# D1MPIXEL.net
KiCad netlist of a schematic drawn in EAGLE
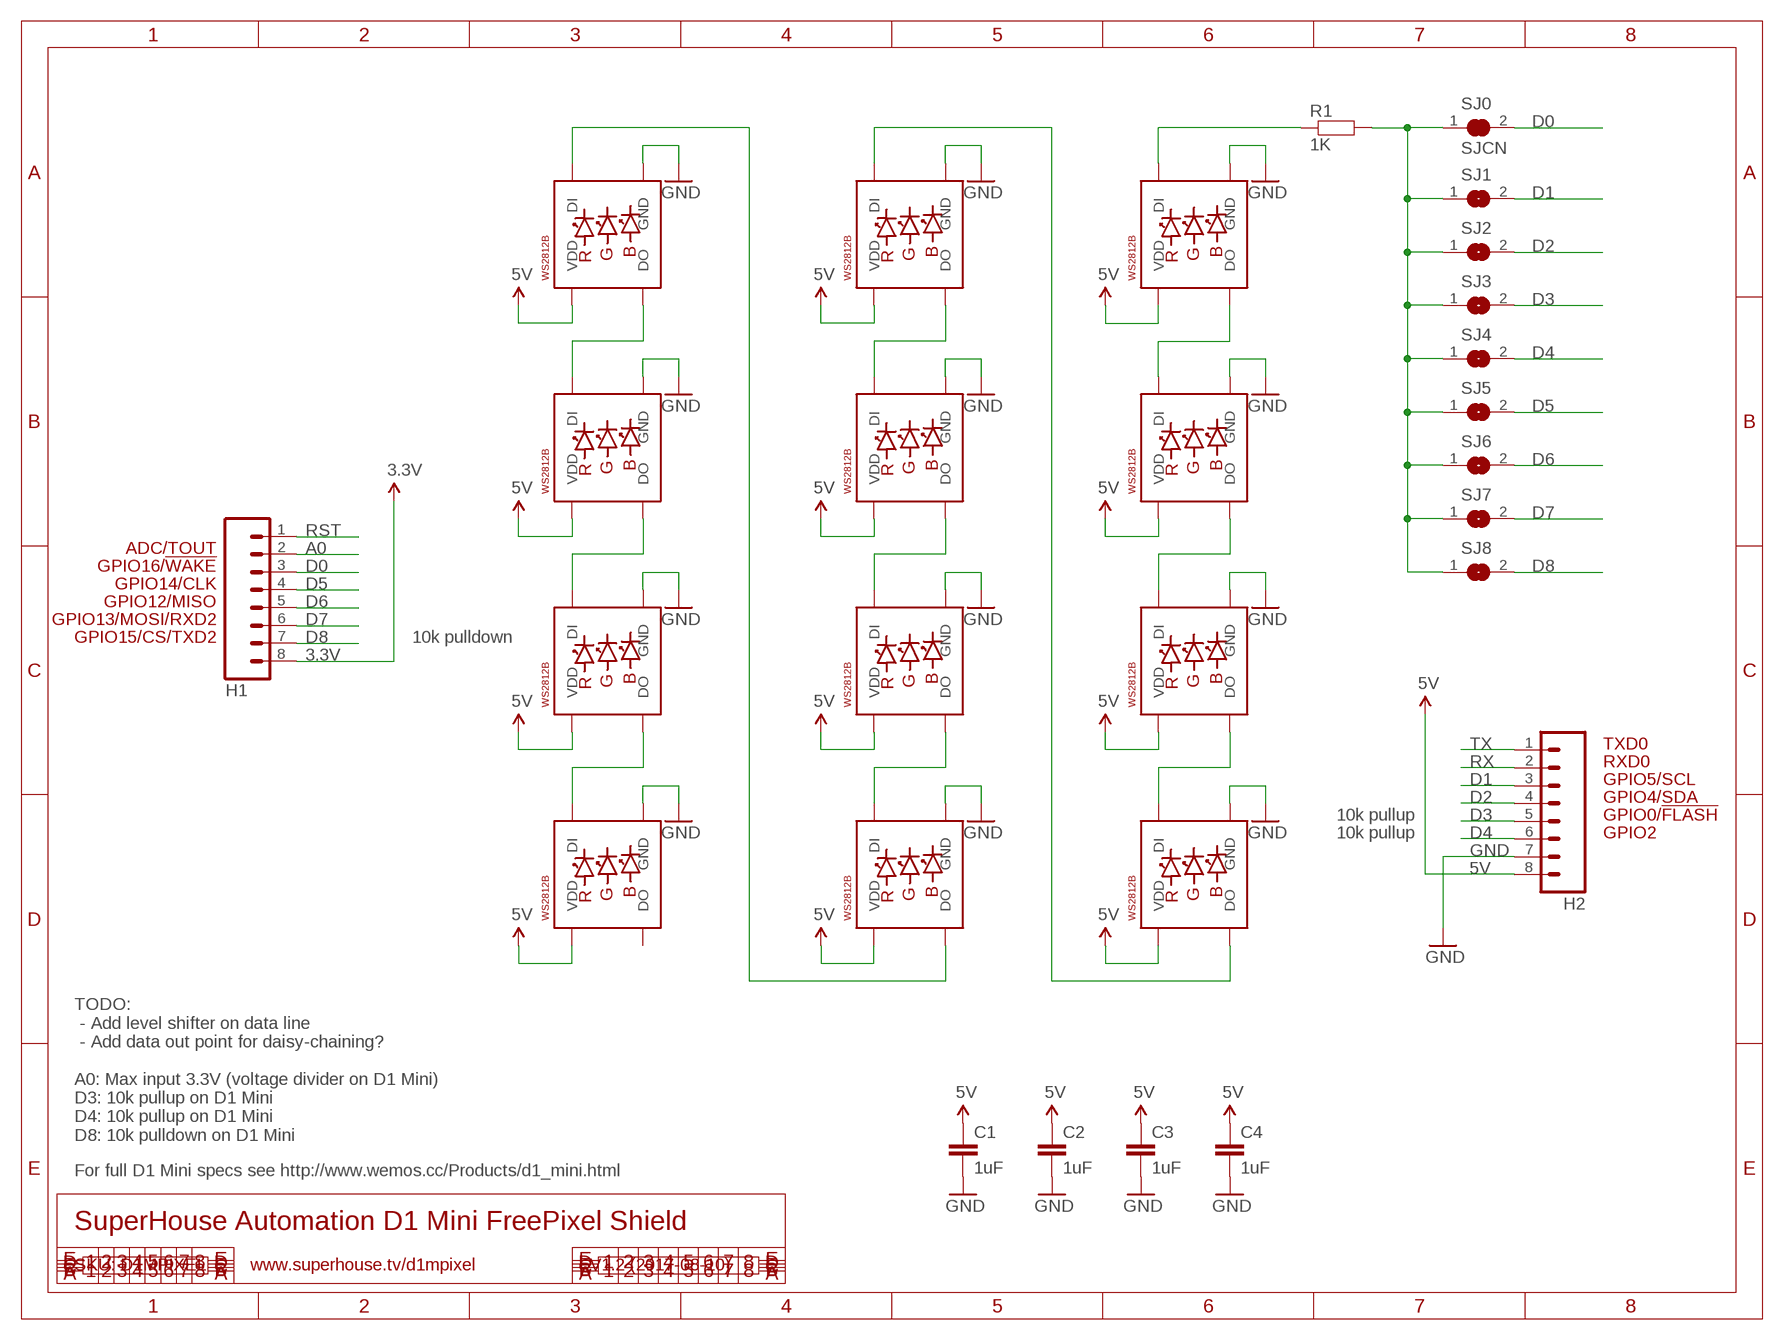
[diagram p0: schematic, sheet 1]

(export (version "E")
  (design (tool "Eeschema 10.0.6"))
  (components
    (comp (ref "C1")
      (value "1uF")
      (footprint "eagle-import:0603")
      (libsource (lib "eagle-import") (part "CAP0603"))
    )
    (comp (ref "C2")
      (value "1uF")
      (footprint "eagle-import:0603")
      (libsource (lib "eagle-import") (part "CAP0603"))
    )
    (comp (ref "C3")
      (value "1uF")
      (footprint "eagle-import:0603")
      (libsource (lib "eagle-import") (part "CAP0603"))
    )
    (comp (ref "C4")
      (value "1uF")
      (footprint "eagle-import:0603")
      (libsource (lib "eagle-import") (part "CAP0603"))
    )
    (comp (ref "H1")
      (value "M08")
      (footprint "eagle-import:1X08")
      (libsource (lib "eagle-import") (part "M08"))
    )
    (comp (ref "H2")
      (value "M08")
      (footprint "eagle-import:1X08")
      (libsource (lib "eagle-import") (part "M08"))
    )
    (comp (ref "LED1")
      (value "WS2812B5050")
      (footprint "eagle-import:WS2812B")
      (libsource (lib "eagle-import") (part "WS2812B5050"))
    )
    (comp (ref "LED2")
      (value "WS2812B5050")
      (footprint "eagle-import:WS2812B")
      (libsource (lib "eagle-import") (part "WS2812B5050"))
    )
    (comp (ref "LED3")
      (value "WS2812B5050")
      (footprint "eagle-import:WS2812B")
      (libsource (lib "eagle-import") (part "WS2812B5050"))
    )
    (comp (ref "LED4")
      (value "WS2812B5050")
      (footprint "eagle-import:WS2812B")
      (libsource (lib "eagle-import") (part "WS2812B5050"))
    )
    (comp (ref "LED5")
      (value "WS2812B5050")
      (footprint "eagle-import:WS2812B")
      (libsource (lib "eagle-import") (part "WS2812B5050"))
    )
    (comp (ref "LED6")
      (value "WS2812B5050")
      (footprint "eagle-import:WS2812B")
      (libsource (lib "eagle-import") (part "WS2812B5050"))
    )
    (comp (ref "LED7")
      (value "WS2812B5050")
      (footprint "eagle-import:WS2812B")
      (libsource (lib "eagle-import") (part "WS2812B5050"))
    )
    (comp (ref "LED8")
      (value "WS2812B5050")
      (footprint "eagle-import:WS2812B")
      (libsource (lib "eagle-import") (part "WS2812B5050"))
    )
    (comp (ref "LED9")
      (value "WS2812B5050")
      (footprint "eagle-import:WS2812B")
      (libsource (lib "eagle-import") (part "WS2812B5050"))
    )
    (comp (ref "LED10")
      (value "WS2812B5050")
      (footprint "eagle-import:WS2812B")
      (libsource (lib "eagle-import") (part "WS2812B5050"))
    )
    (comp (ref "LED11")
      (value "WS2812B5050")
      (footprint "eagle-import:WS2812B")
      (libsource (lib "eagle-import") (part "WS2812B5050"))
    )
    (comp (ref "LED12")
      (value "WS2812B5050")
      (footprint "eagle-import:WS2812B")
      (libsource (lib "eagle-import") (part "WS2812B5050"))
    )
    (comp (ref "R1")
      (value "1K")
      (footprint "eagle-import:0603")
      (libsource (lib "eagle-import") (part "RESISTOR0603"))
    )
    (comp (ref "SJ0")
      (value "SJCN")
      (footprint "eagle-import:SJC")
      (libsource (lib "eagle-import") (part "SJCN"))
    )
    (comp (ref "SJ1")
      (value "SJN")
      (footprint "eagle-import:SJ")
      (libsource (lib "eagle-import") (part "SJN"))
    )
    (comp (ref "SJ2")
      (value "SJN")
      (footprint "eagle-import:SJ")
      (libsource (lib "eagle-import") (part "SJN"))
    )
    (comp (ref "SJ3")
      (value "SJN")
      (footprint "eagle-import:SJ")
      (libsource (lib "eagle-import") (part "SJN"))
    )
    (comp (ref "SJ4")
      (value "SJN")
      (footprint "eagle-import:SJ")
      (libsource (lib "eagle-import") (part "SJN"))
    )
    (comp (ref "SJ5")
      (value "SJN")
      (footprint "eagle-import:SJ")
      (libsource (lib "eagle-import") (part "SJN"))
    )
    (comp (ref "SJ6")
      (value "SJN")
      (footprint "eagle-import:SJ")
      (libsource (lib "eagle-import") (part "SJN"))
    )
    (comp (ref "SJ7")
      (value "SJN")
      (footprint "eagle-import:SJ")
      (libsource (lib "eagle-import") (part "SJN"))
    )
    (comp (ref "SJ8")
      (value "SJN")
      (footprint "eagle-import:SJ")
      (libsource (lib "eagle-import") (part "SJN"))
    )
  )
  (nets
    (net (code "1") (name "/A0") (class "Default")
      (node (ref "H1") (pin "2") (pinfunction "2_2") (pintype "passive"))
    )
    (net (code "2") (name "/D0") (class "Default")
      (node (ref "H1") (pin "3") (pinfunction "3_3") (pintype "passive"))
      (node (ref "SJ0") (pin "2") (pinfunction "2_2") (pintype "passive"))
    )
    (net (code "3") (name "/D1") (class "Default")
      (node (ref "H2") (pin "3") (pinfunction "3_3") (pintype "passive"))
      (node (ref "SJ1") (pin "2") (pinfunction "2_2") (pintype "passive"))
    )
    (net (code "4") (name "/D2") (class "Default")
      (node (ref "H2") (pin "4") (pinfunction "4_4") (pintype "passive"))
      (node (ref "SJ2") (pin "2") (pinfunction "2_2") (pintype "passive"))
    )
    (net (code "5") (name "/D3") (class "Default")
      (node (ref "H2") (pin "5") (pinfunction "5_5") (pintype "passive"))
      (node (ref "SJ3") (pin "2") (pinfunction "2_2") (pintype "passive"))
    )
    (net (code "6") (name "/D4") (class "Default")
      (node (ref "H2") (pin "6") (pinfunction "6_6") (pintype "passive"))
      (node (ref "SJ4") (pin "2") (pinfunction "2_2") (pintype "passive"))
    )
    (net (code "7") (name "/D5") (class "Default")
      (node (ref "H1") (pin "4") (pinfunction "4_4") (pintype "passive"))
      (node (ref "SJ5") (pin "2") (pinfunction "2_2") (pintype "passive"))
    )
    (net (code "8") (name "/D6") (class "Default")
      (node (ref "H1") (pin "5") (pinfunction "5_5") (pintype "passive"))
      (node (ref "SJ6") (pin "2") (pinfunction "2_2") (pintype "passive"))
    )
    (net (code "9") (name "/D7") (class "Default")
      (node (ref "H1") (pin "6") (pinfunction "6_6") (pintype "passive"))
      (node (ref "SJ7") (pin "2") (pinfunction "2_2") (pintype "passive"))
    )
    (net (code "10") (name "/D8") (class "Default")
      (node (ref "H1") (pin "7") (pinfunction "7_7") (pintype "passive"))
      (node (ref "SJ8") (pin "2") (pinfunction "2_2") (pintype "passive"))
    )
    (net (code "11") (name "/RST") (class "Default")
      (node (ref "H1") (pin "1") (pinfunction "1_1") (pintype "passive"))
    )
    (net (code "12") (name "/RX") (class "Default")
      (node (ref "H2") (pin "2") (pinfunction "2_2") (pintype "passive"))
    )
    (net (code "13") (name "/TX") (class "Default")
      (node (ref "H2") (pin "1") (pinfunction "1_1") (pintype "passive"))
    )
    (net (code "14") (name "3.3V") (class "Default")
      (node (ref "H1") (pin "8") (pinfunction "8_8") (pintype "passive"))
    )
    (net (code "15") (name "5V") (class "Default")
      (node (ref "C1") (pin "1") (pinfunction "1_1") (pintype "passive"))
      (node (ref "C2") (pin "1") (pinfunction "1_1") (pintype "passive"))
      (node (ref "C3") (pin "1") (pinfunction "1_1") (pintype "passive"))
      (node (ref "C4") (pin "1") (pinfunction "1_1") (pintype "passive"))
      (node (ref "H2") (pin "8") (pinfunction "8_8") (pintype "passive"))
      (node (ref "LED1") (pin "1-VDD") (pinfunction "VDD_1-VDD") (pintype "power_in"))
      (node (ref "LED10") (pin "1-VDD") (pinfunction "VDD_1-VDD") (pintype "power_in"))
      (node (ref "LED11") (pin "1-VDD") (pinfunction "VDD_1-VDD") (pintype "power_in"))
      (node (ref "LED12") (pin "1-VDD") (pinfunction "VDD_1-VDD") (pintype "power_in"))
      (node (ref "LED2") (pin "1-VDD") (pinfunction "VDD_1-VDD") (pintype "power_in"))
      (node (ref "LED3") (pin "1-VDD") (pinfunction "VDD_1-VDD") (pintype "power_in"))
      (node (ref "LED4") (pin "1-VDD") (pinfunction "VDD_1-VDD") (pintype "power_in"))
      (node (ref "LED5") (pin "1-VDD") (pinfunction "VDD_1-VDD") (pintype "power_in"))
      (node (ref "LED6") (pin "1-VDD") (pinfunction "VDD_1-VDD") (pintype "power_in"))
      (node (ref "LED7") (pin "1-VDD") (pinfunction "VDD_1-VDD") (pintype "power_in"))
      (node (ref "LED8") (pin "1-VDD") (pinfunction "VDD_1-VDD") (pintype "power_in"))
      (node (ref "LED9") (pin "1-VDD") (pinfunction "VDD_1-VDD") (pintype "power_in"))
    )
    (net (code "16") (name "GND") (class "Default")
      (node (ref "C1") (pin "2") (pinfunction "2_2") (pintype "passive"))
      (node (ref "C2") (pin "2") (pinfunction "2_2") (pintype "passive"))
      (node (ref "C3") (pin "2") (pinfunction "2_2") (pintype "passive"))
      (node (ref "C4") (pin "2") (pinfunction "2_2") (pintype "passive"))
      (node (ref "H2") (pin "7") (pinfunction "7_7") (pintype "passive"))
      (node (ref "LED1") (pin "3-GND") (pinfunction "GND_3-GND") (pintype "power_in"))
      (node (ref "LED10") (pin "3-GND") (pinfunction "GND_3-GND") (pintype "power_in"))
      (node (ref "LED11") (pin "3-GND") (pinfunction "GND_3-GND") (pintype "power_in"))
      (node (ref "LED12") (pin "3-GND") (pinfunction "GND_3-GND") (pintype "power_in"))
      (node (ref "LED2") (pin "3-GND") (pinfunction "GND_3-GND") (pintype "power_in"))
      (node (ref "LED3") (pin "3-GND") (pinfunction "GND_3-GND") (pintype "power_in"))
      (node (ref "LED4") (pin "3-GND") (pinfunction "GND_3-GND") (pintype "power_in"))
      (node (ref "LED5") (pin "3-GND") (pinfunction "GND_3-GND") (pintype "power_in"))
      (node (ref "LED6") (pin "3-GND") (pinfunction "GND_3-GND") (pintype "power_in"))
      (node (ref "LED7") (pin "3-GND") (pinfunction "GND_3-GND") (pintype "power_in"))
      (node (ref "LED8") (pin "3-GND") (pinfunction "GND_3-GND") (pintype "power_in"))
      (node (ref "LED9") (pin "3-GND") (pinfunction "GND_3-GND") (pintype "power_in"))
    )
    (net (code "17") (name "Net-(LED1-DI)") (class "Default")
      (node (ref "LED1") (pin "4-DIN") (pinfunction "DI_4-DIN") (pintype "input"))
      (node (ref "R1") (pin "1") (pinfunction "1_1") (pintype "passive"))
    )
    (net (code "18") (name "Net-(LED1-DO)") (class "Default")
      (node (ref "LED1") (pin "2-DOUT") (pinfunction "DO_2-DOUT") (pintype "output"))
      (node (ref "LED2") (pin "4-DIN") (pinfunction "DI_4-DIN") (pintype "input"))
    )
    (net (code "19") (name "Net-(LED2-DO)") (class "Default")
      (node (ref "LED2") (pin "2-DOUT") (pinfunction "DO_2-DOUT") (pintype "output"))
      (node (ref "LED3") (pin "4-DIN") (pinfunction "DI_4-DIN") (pintype "input"))
    )
    (net (code "20") (name "Net-(LED3-DO)") (class "Default")
      (node (ref "LED3") (pin "2-DOUT") (pinfunction "DO_2-DOUT") (pintype "output"))
      (node (ref "LED4") (pin "4-DIN") (pinfunction "DI_4-DIN") (pintype "input"))
    )
    (net (code "21") (name "Net-(LED4-DO)") (class "Default")
      (node (ref "LED4") (pin "2-DOUT") (pinfunction "DO_2-DOUT") (pintype "output"))
      (node (ref "LED5") (pin "4-DIN") (pinfunction "DI_4-DIN") (pintype "input"))
    )
    (net (code "22") (name "Net-(LED5-DO)") (class "Default")
      (node (ref "LED5") (pin "2-DOUT") (pinfunction "DO_2-DOUT") (pintype "output"))
      (node (ref "LED6") (pin "4-DIN") (pinfunction "DI_4-DIN") (pintype "input"))
    )
    (net (code "23") (name "Net-(LED6-DO)") (class "Default")
      (node (ref "LED6") (pin "2-DOUT") (pinfunction "DO_2-DOUT") (pintype "output"))
      (node (ref "LED7") (pin "4-DIN") (pinfunction "DI_4-DIN") (pintype "input"))
    )
    (net (code "24") (name "Net-(LED7-DO)") (class "Default")
      (node (ref "LED7") (pin "2-DOUT") (pinfunction "DO_2-DOUT") (pintype "output"))
      (node (ref "LED8") (pin "4-DIN") (pinfunction "DI_4-DIN") (pintype "input"))
    )
    (net (code "25") (name "Net-(LED8-DO)") (class "Default")
      (node (ref "LED8") (pin "2-DOUT") (pinfunction "DO_2-DOUT") (pintype "output"))
      (node (ref "LED9") (pin "4-DIN") (pinfunction "DI_4-DIN") (pintype "input"))
    )
    (net (code "26") (name "Net-(LED10-DI)") (class "Default")
      (node (ref "LED10") (pin "4-DIN") (pinfunction "DI_4-DIN") (pintype "input"))
      (node (ref "LED9") (pin "2-DOUT") (pinfunction "DO_2-DOUT") (pintype "output"))
    )
    (net (code "27") (name "Net-(LED10-DO)") (class "Default")
      (node (ref "LED10") (pin "2-DOUT") (pinfunction "DO_2-DOUT") (pintype "output"))
      (node (ref "LED11") (pin "4-DIN") (pinfunction "DI_4-DIN") (pintype "input"))
    )
    (net (code "28") (name "Net-(LED11-DO)") (class "Default")
      (node (ref "LED11") (pin "2-DOUT") (pinfunction "DO_2-DOUT") (pintype "output"))
      (node (ref "LED12") (pin "4-DIN") (pinfunction "DI_4-DIN") (pintype "input"))
    )
    (net (code "29") (name "Net-(R1-Pad2)") (class "Default")
      (node (ref "R1") (pin "2") (pinfunction "2_2") (pintype "passive"))
      (node (ref "SJ0") (pin "1") (pinfunction "1_1") (pintype "passive"))
      (node (ref "SJ1") (pin "1") (pinfunction "1_1") (pintype "passive"))
      (node (ref "SJ2") (pin "1") (pinfunction "1_1") (pintype "passive"))
      (node (ref "SJ3") (pin "1") (pinfunction "1_1") (pintype "passive"))
      (node (ref "SJ4") (pin "1") (pinfunction "1_1") (pintype "passive"))
      (node (ref "SJ5") (pin "1") (pinfunction "1_1") (pintype "passive"))
      (node (ref "SJ6") (pin "1") (pinfunction "1_1") (pintype "passive"))
      (node (ref "SJ7") (pin "1") (pinfunction "1_1") (pintype "passive"))
      (node (ref "SJ8") (pin "1") (pinfunction "1_1") (pintype "passive"))
    )
    (net (code "30") (name "unconnected-(LED12-DO-Pad2-DOUT)") (class "Default")
      (node (ref "LED12") (pin "2-DOUT") (pinfunction "DO_2-DOUT") (pintype "output"))
    )
  )
)
